# Sheet_SiPM.net
KiCad netlist of a schematic drawn in Altium Designer
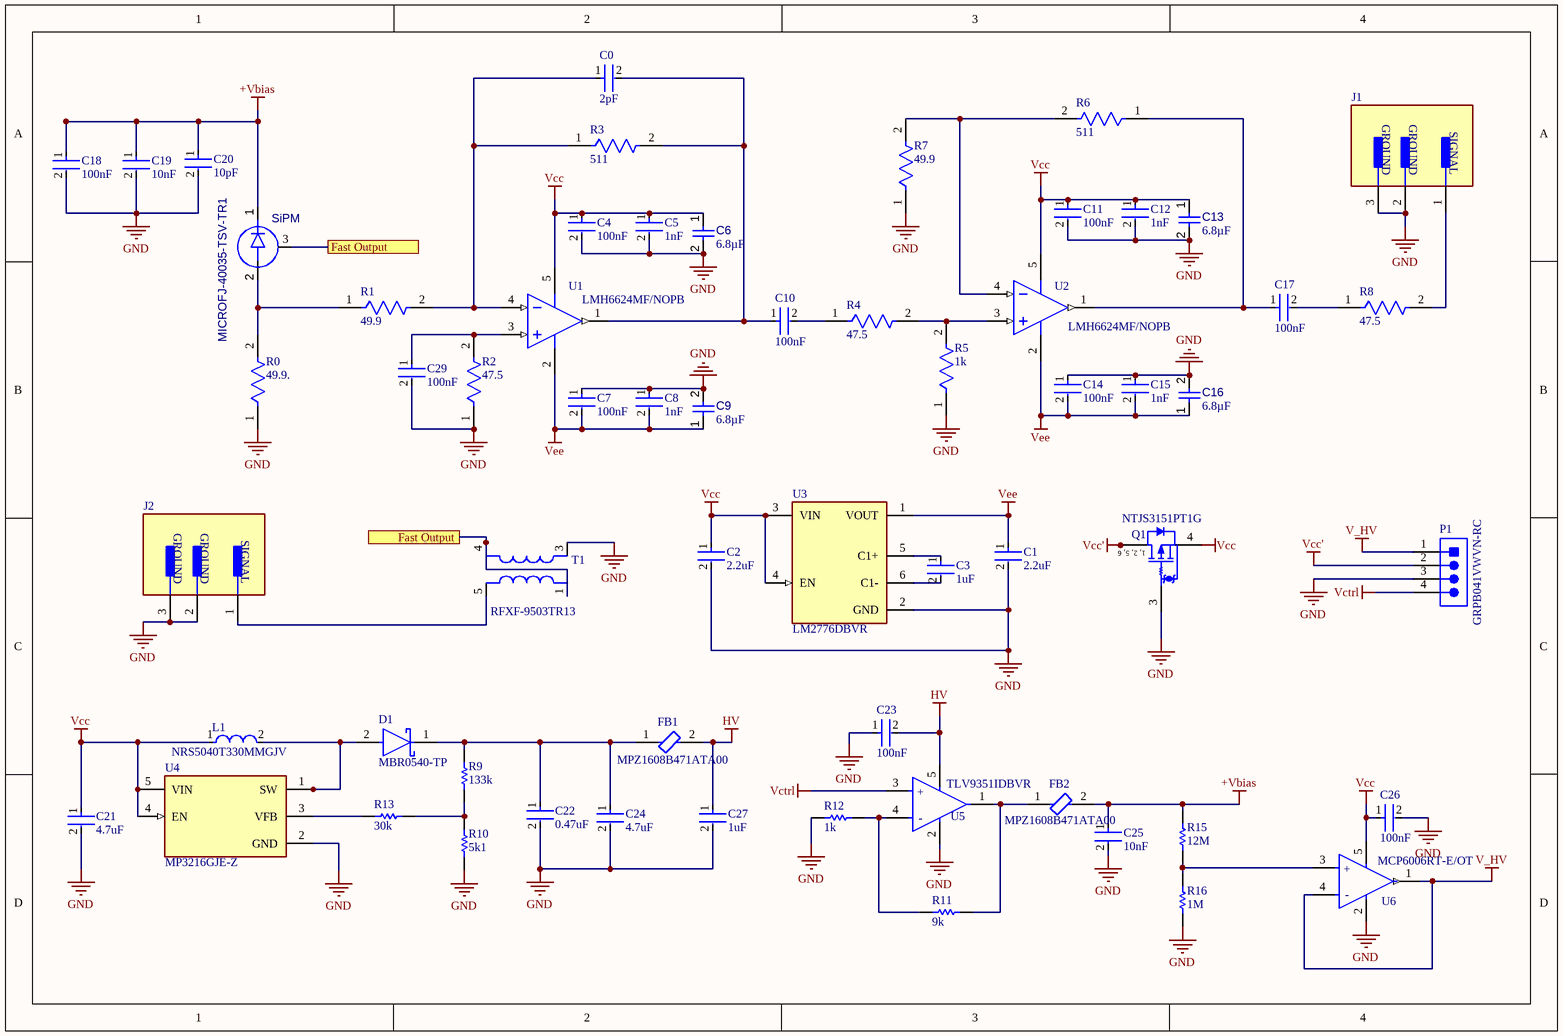
[diagram p0: Sheet_SiPM.SchDoc]

(export (version "E")
  (design (tool "Eeschema 10.0.6"))
  (components
    (comp (ref "C0")
      (value "2pF")
      (footprint "FP-0603-L_1_6_0_15-W_0_81-MFG")
      (description "General Purpose Ceramic Capacitor, 0603, 1pF, 0.1pF, NP0, 30ppm/°C, 50V")
      (libsource (lib "Altium Content Vault") (part "02cd4be3c70576c341d710602a673aa"))
    )
    (comp (ref "C1")
      (value "2.2uF")
      (footprint "FP-GRM188-0_2-MFG")
      (description "Chip Multilayer Ceramic Capacitors for General Purpose, 0603, 2.2uF, X7R, 15%, 10%, 16V")
      (libsource (lib "Altium Content Vault") (part "11868f565c42a9108669ba33697ecf6"))
    )
    (comp (ref "C2")
      (value "2.2uF")
      (footprint "FP-GRM188-0_2-MFG")
      (description "Chip Multilayer Ceramic Capacitors for General Purpose, 0603, 2.2uF, X7R, 15%, 10%, 16V")
      (libsource (lib "Altium Content Vault") (part "11868f565c42a9108669ba33697ecf6"))
    )
    (comp (ref "C3")
      (value "1uF")
      (footprint "FP-CC0603-DA-MFG")
      (description "CAP CER 1UF 16V X7R 0603")
      (fields (field (name "TOLERANCE") "0.1") (field (name "MANUFACTURER") "YAGEO"))
      (libsource (lib "Altium Content Vault") (part "11868f565c42a9108669ba33697ecf6"))
    )
    (comp (ref "C4")
      (value "100nF")
      (footprint "FP-CC0603-DA-MFG")
      (description "CAP CER 0.1UF 16V X7R 0603")
      (fields
        (field (name "OCTOPART") "https://octopart.com/cc0603krx7r7bb104-yageo-192941")
        (field (name "TOLERANCE") "0.1")
      )
      (libsource (lib "Altium Content Vault") (part "11868f565c42a9108669ba33697ecf6"))
    )
    (comp (ref "C5")
      (value "1nF")
      (footprint "FP-CC0603-DA-MFG")
      (description "CAP CER 1000PF 25V X7R 0603")
      (fields
        (field (name "MANUFACTURER") "YAGEO")
        (field (name "OCTOPART") "https://octopart.com/cc0603krx7r8bb102-yageo-9291798")
      )
      (libsource (lib "Altium Content Vault") (part "11868f565c42a9108669ba33697ecf6"))
    )
    (comp (ref "C6")
      (value "6.8µF")
      (footprint "TPSA685K016R1500-Footprint-1")
      (fields (field (name "Comment") "TPSA685K016R1500"))
      (libsource (lib "Francisco Martinez") (part "CAP-NP-2"))
    )
    (comp (ref "C7")
      (value "100nF")
      (footprint "FP-CC0603-DA-MFG")
      (description "CAP CER 0.1UF 16V X7R 0603")
      (fields
        (field (name "OCTOPART") "https://octopart.com/cc0603krx7r7bb104-yageo-192941")
        (field (name "TOLERANCE") "0.1")
      )
      (libsource (lib "Altium Content Vault") (part "11868f565c42a9108669ba33697ecf6"))
    )
    (comp (ref "C8")
      (value "1nF")
      (footprint "FP-CC0603-DA-MFG")
      (description "CAP CER 1000PF 25V X7R 0603")
      (fields
        (field (name "MANUFACTURER") "YAGEO")
        (field (name "OCTOPART") "https://octopart.com/cc0603krx7r8bb102-yageo-9291798")
      )
      (libsource (lib "Altium Content Vault") (part "11868f565c42a9108669ba33697ecf6"))
    )
    (comp (ref "C9")
      (value "6.8µF")
      (footprint "TPSA685K016R1500-Footprint-1")
      (fields (field (name "Comment") "TPSA685K016R1500"))
      (libsource (lib "Francisco Martinez") (part "CAP-NP-2"))
    )
    (comp (ref "C10")
      (value "100nF")
      (footprint "FP-CC0603-DA-MFG")
      (description "CAP CER 0.1UF 16V X7R 0603")
      (fields
        (field (name "OCTOPART") "https://octopart.com/cc0603krx7r7bb104-yageo-192941")
        (field (name "TOLERANCE") "0.1")
      )
      (libsource (lib "Altium Content Vault") (part "11868f565c42a9108669ba33697ecf6"))
    )
    (comp (ref "C11")
      (value "100nF")
      (footprint "FP-CC0603-DA-MFG")
      (description "CAP CER 0.1UF 16V X7R 0603")
      (fields
        (field (name "OCTOPART") "https://octopart.com/cc0603krx7r7bb104-yageo-192941")
        (field (name "TOLERANCE") "0.1")
      )
      (libsource (lib "Altium Content Vault") (part "11868f565c42a9108669ba33697ecf6"))
    )
    (comp (ref "C12")
      (value "1nF")
      (footprint "FP-CC0603-DA-MFG")
      (description "CAP CER 1000PF 25V X7R 0603")
      (fields
        (field (name "MANUFACTURER") "YAGEO")
        (field (name "OCTOPART") "https://octopart.com/cc0603krx7r8bb102-yageo-9291798")
      )
      (libsource (lib "Altium Content Vault") (part "11868f565c42a9108669ba33697ecf6"))
    )
    (comp (ref "C13")
      (value "6.8µF")
      (footprint "TPSA685K016R1500-Footprint-1")
      (fields (field (name "Comment") "TPSA685K016R1500"))
      (libsource (lib "Francisco Martinez") (part "CAP-NP-2"))
    )
    (comp (ref "C14")
      (value "100nF")
      (footprint "FP-CC0603-DA-MFG")
      (description "CAP CER 0.1UF 16V X7R 0603")
      (fields
        (field (name "OCTOPART") "https://octopart.com/cc0603krx7r7bb104-yageo-192941")
        (field (name "TOLERANCE") "0.1")
      )
      (libsource (lib "Altium Content Vault") (part "11868f565c42a9108669ba33697ecf6"))
    )
    (comp (ref "C15")
      (value "1nF")
      (footprint "FP-CC0603-DA-MFG")
      (description "CAP CER 1000PF 25V X7R 0603")
      (fields
        (field (name "MANUFACTURER") "YAGEO")
        (field (name "OCTOPART") "https://octopart.com/cc0603krx7r8bb102-yageo-9291798")
      )
      (libsource (lib "Altium Content Vault") (part "11868f565c42a9108669ba33697ecf6"))
    )
    (comp (ref "C16")
      (value "6.8µF")
      (footprint "TPSA685K016R1500-Footprint-1")
      (fields (field (name "Comment") "TPSA685K016R1500"))
      (libsource (lib "Francisco Martinez") (part "CAP-NP-2"))
    )
    (comp (ref "C17")
      (value "100nF")
      (footprint "FP-CC0603-DA-MFG")
      (description "CAP CER 0.1UF 16V X7R 0603")
      (fields
        (field (name "OCTOPART") "https://octopart.com/cc0603krx7r7bb104-yageo-192941")
        (field (name "TOLERANCE") "0.1")
      )
      (libsource (lib "Altium Content Vault") (part "11868f565c42a9108669ba33697ecf6"))
    )
    (comp (ref "C18")
      (value "100nF")
      (footprint "FP-CC0603-DA-MFG")
      (description "CAP CER 0.1UF 50V X7R 0603")
      (fields (field (name "MANUFACTURER") "YAGEO") (field (name "VOLTAGE") "50 V"))
      (libsource (lib "Altium Content Vault") (part "11868f565c42a9108669ba33697ecf6"))
    )
    (comp (ref "C19")
      (value "10nF")
      (footprint "FP-CC0603-DA-MFG")
      (description "CAP CER 10000PF 50V X7R 0603")
      (fields (field (name "TOLERANCE") "0.1") (field (name "MANUFACTURER PART NUMBER") "CC0603KRX7R9BB103"))
      (libsource (lib "Altium Content Vault") (part "11868f565c42a9108669ba33697ecf6"))
    )
    (comp (ref "C20")
      (value "10pF")
      (footprint "FP-AC0603-MFG")
      (description "AC0603 10 pF NP0 1.00% 50 V")
      (fields
        (field (name "MANUFACTURER") "Yageo")
        (field (name "MANUFACTURER PART NUMBER") "AC0603FRNPO9BN100")
      )
      (libsource (lib "Altium Content Vault") (part "11868f565c42a9108669ba33697ecf6"))
    )
    (comp (ref "C21")
      (value "4.7uF")
      (footprint "FP-0603-L_1_6_0_1-W_0_8_0-MFG")
      (description "Ceramic Capacitor General Use 0.47uF ±10% 50V X7R 0603")
      (fields (field (name "VOLTAGE") "50V") (field (name "TOLERANCE") "10%"))
      (libsource (lib "Altium Content Vault") (part "02cd4be3c70576c341d710602a673aa"))
    )
    (comp (ref "C22")
      (value "0.47uF")
      (footprint "FP-0603-L_1_6_0_1-W_0_8_0-MFG")
      (description "Ceramic Capacitor General Use 0.47uF ±10% 50V X7R 0603")
      (fields (field (name "VOLTAGE") "50V") (field (name "TOLERANCE") "10%"))
      (libsource (lib "Altium Content Vault") (part "02cd4be3c70576c341d710602a673aa"))
    )
    (comp (ref "C23")
      (value "100nF")
      (footprint "FP-CC0603-DA-MFG")
      (description "CAP CER 0.1UF 50V X7R 0603")
      (fields (field (name "MANUFACTURER") "YAGEO") (field (name "VOLTAGE") "50 V"))
      (libsource (lib "Altium Content Vault") (part "11868f565c42a9108669ba33697ecf6"))
    )
    (comp (ref "C24")
      (value "4.7uF")
      (footprint "FP-0603-L_1_6_0_15-W_0_8-MFG")
      (description "Ceramic Capacitor General Use 1uF ±10% 50V X7R 0603")
      (fields (field (name "TOLERANCE") "10%"))
      (libsource (lib "Altium Content Vault") (part "11868f565c42a9108669ba33697ecf6"))
    )
    (comp (ref "C25")
      (value "10nF")
      (footprint "FP-CC0603-DA-MFG")
      (description "CAP CER 10000PF 50V X7R 0603")
      (fields (field (name "TOLERANCE") "0.1") (field (name "MANUFACTURER PART NUMBER") "CC0603KRX7R9BB103"))
      (libsource (lib "Altium Content Vault") (part "11868f565c42a9108669ba33697ecf6"))
    )
    (comp (ref "C26")
      (value "100nF")
      (footprint "FP-CC0603-DA-MFG")
      (description "CAP CER 0.1UF 16V X7R 0603")
      (fields
        (field (name "OCTOPART") "https://octopart.com/cc0603krx7r7bb104-yageo-192941")
        (field (name "TOLERANCE") "0.1")
      )
      (libsource (lib "Altium Content Vault") (part "11868f565c42a9108669ba33697ecf6"))
    )
    (comp (ref "C27")
      (value "1uF")
      (footprint "FP-CC0603-DA-MFG")
      (description "CAP CER 10000PF 50V X7R 0603")
      (fields (field (name "TOLERANCE") "0.1") (field (name "MANUFACTURER PART NUMBER") "CC0603KRX7R9BB103"))
      (libsource (lib "Altium Content Vault") (part "11868f565c42a9108669ba33697ecf6"))
    )
    (comp (ref "C29")
      (value "100nF")
      (footprint "FP-CC0603-DA-MFG")
      (description "CAP CER 0.1UF 16V X7R 0603")
      (fields
        (field (name "OCTOPART") "https://octopart.com/cc0603krx7r7bb104-yageo-192941")
        (field (name "TOLERANCE") "0.1")
      )
      (libsource (lib "Altium Content Vault") (part "11868f565c42a9108669ba33697ecf6"))
    )
    (comp (ref "D1")
      (value "MBR0540-TP")
      (footprint "FP-SOD-123-MFG")
      (description "DIODE SCHOTTKY 40V 500MA SOD123")
      (libsource (lib "Altium Content Vault") (part "1d6ec82d83fb6aee721767c19dac4b9"))
    )
    (comp (ref "FB1")
      (value "MPZ1608B471ATA00")
      (footprint "FP-MPZ1608-0_8-MFG")
      (description "Power line Ferrite Bead 470Ω @ 100MHz 1A DCR 0.15Ω SMD 0603")
      (fields (field (name "TOLERANCE") "25%"))
      (libsource (lib "Altium Content Vault") (part "5f30dd21d616792df468990f7003faa"))
    )
    (comp (ref "FB2")
      (value "MPZ1608B471ATA00")
      (footprint "FP-MPZ1608-0_8-MFG")
      (description "Power line Ferrite Bead 470Ω @ 100MHz 1A DCR 0.15Ω SMD 0603")
      (fields (field (name "TOLERANCE") "25%"))
      (libsource (lib "Altium Content Vault") (part "5f30dd21d616792df468990f7003faa"))
    )
    (comp (ref "J1")
      (value "2337019-1")
      (footprint "FP-2337019-1-MFG")
      (description "UMCC MICRO-COAX RECEPTACLE, GEN")
      (libsource (lib "Altium Content Vault") (part "3efd87c86022015edd7e825a7948772"))
    )
    (comp (ref "J2")
      (value "2337019-1")
      (footprint "FP-2337019-1-MFG")
      (description "UMCC MICRO-COAX RECEPTACLE, GEN")
      (libsource (lib "Altium Content Vault") (part "3efd87c86022015edd7e825a7948772"))
    )
    (comp (ref "L1")
      (value "NRS5040T330MMGJV")
      (footprint "FP-NR5040-H_4_0-MFG")
      (description "SMD Power Inductors for Automotive Applications 33uH ±20% 1.2A 0.234Ω")
      (fields (field (name "TOLERANCE") "20%"))
      (libsource (lib "Altium Content Vault") (part "725321dda6339637d4d059423bc1c3c"))
    )
    (comp (ref "P1")
      (value "GRPB041VWVN-RC")
      (footprint "SLIN-GRPB041VWVN-RC_V")
      (fields (field (name "MANUFACTURER") "Sullins"))
      (libsource (lib "Altium Content Vault") (part "CN-1P-M-R4"))
    )
    (comp (ref "Q1")
      (value "NTJS3151PT1G")
      (footprint "ONSC-SC70-6-419B-02_W_V")
      (fields (field (name "MANUFACTURER") "On Semiconductor"))
      (libsource (lib "Altium Content Vault") (part "ONSC-PMOS-6_D"))
    )
    (comp (ref "R0")
      (value "49.9.")
      (footprint "FP-RNCP0603-MFG")
      (description "49.9Ω ±1% 0.125W 0603 High Power Anti-Sulfur Thin Film Chip Resistor")
      (fields (field (name "TOLERANCE") "1%"))
      (libsource (lib "Altium Content Vault") (part "1029c3af85768c4190bb7ad29bc67b5"))
    )
    (comp (ref "R1")
      (value "49.9")
      (footprint "FP-RNCP0603-MFG")
      (description "49.9Ω ±1% 0.125W 0603 High Power Anti-Sulfur Thin Film Chip Resistor")
      (fields (field (name "TOLERANCE") "1%"))
      (libsource (lib "Altium Content Vault") (part "1029c3af85768c4190bb7ad29bc67b5"))
    )
    (comp (ref "R2")
      (value "47.5")
      (footprint "FP-RNCP0603-MFG")
      (description "47.5Ω ±1% 0.125W 0603 High Power Anti-Sulfur Thin Film Chip Resistor")
      (fields (field (name "TOLERANCE") "1%"))
      (libsource (lib "Altium Content Vault") (part "1029c3af85768c4190bb7ad29bc67b5"))
    )
    (comp (ref "R3")
      (value "511")
      (footprint "FP-MCT0603-MFG")
      (description "RES SMD 100 OHM 1% 1/8W 0603")
      (fields (field (name "TOLERANCE") "1%"))
      (libsource (lib "Altium Content Vault") (part "1029c3af85768c4190bb7ad29bc67b5"))
    )
    (comp (ref "R4")
      (value "47.5")
      (footprint "FP-RNCP0603-MFG")
      (description "47.5Ω ±1% 0.125W 0603 High Power Anti-Sulfur Thin Film Chip Resistor")
      (fields (field (name "TOLERANCE") "1%"))
      (libsource (lib "Altium Content Vault") (part "1029c3af85768c4190bb7ad29bc67b5"))
    )
    (comp (ref "R5")
      (value "1k")
      (footprint "FP-MCT0603-MFG")
      (description "RES SMD 100 OHM 1% 1/8W 0603")
      (fields (field (name "TOLERANCE") "1%"))
      (libsource (lib "Altium Content Vault") (part "1029c3af85768c4190bb7ad29bc67b5"))
    )
    (comp (ref "R6")
      (value "511")
      (footprint "FP-MCT0603-MFG")
      (description "RES SMD 100 OHM 1% 1/8W 0603")
      (fields (field (name "TOLERANCE") "1%"))
      (libsource (lib "Altium Content Vault") (part "1029c3af85768c4190bb7ad29bc67b5"))
    )
    (comp (ref "R7")
      (value "49.9")
      (footprint "FP-RNCP0603-MFG")
      (description "49.9Ω ±1% 0.125W 0603 High Power Anti-Sulfur Thin Film Chip Resistor")
      (fields (field (name "TOLERANCE") "1%"))
      (libsource (lib "Altium Content Vault") (part "1029c3af85768c4190bb7ad29bc67b5"))
    )
    (comp (ref "R8")
      (value "47.5")
      (footprint "FP-RNCP0603-MFG")
      (description "47.5Ω ±1% 0.125W 0603 High Power Anti-Sulfur Thin Film Chip Resistor")
      (fields (field (name "TOLERANCE") "1%"))
      (libsource (lib "Altium Content Vault") (part "1029c3af85768c4190bb7ad29bc67b5"))
    )
    (comp (ref "R9")
      (value "133k")
      (footprint "RESC2013X60X35LL10T20")
      (fields (field (name "MANUFACTURER") "Yageo") (field (name "PART NUMBER") "RC0805FR-071M05L"))
      (libsource (lib "Altium Content Vault") (part "RES"))
    )
    (comp (ref "R10")
      (value "5k1")
      (footprint "RESC2013X60X35LL10T20")
      (fields (field (name "MANUFACTURER") "Yageo") (field (name "PART NUMBER") "RC0805JR-0743KL"))
      (libsource (lib "Altium Content Vault") (part "RES"))
    )
    (comp (ref "R11")
      (value "9k")
      (footprint "RESC2013X60X35LL10T20")
      (fields (field (name "MANUFACTURER") "Yageo") (field (name "PART NUMBER") "RC0805FR-071M05L"))
      (libsource (lib "Altium Content Vault") (part "RES"))
    )
    (comp (ref "R12")
      (value "1k")
      (footprint "RESC2013X60X35LL10T20")
      (fields (field (name "MANUFACTURER") "Yageo") (field (name "PART NUMBER") "RC0805FR-071M05L"))
      (libsource (lib "Altium Content Vault") (part "RES"))
    )
    (comp (ref "R13")
      (value "30k")
      (footprint "RESC2013X60X35LL10T20")
      (fields (field (name "MANUFACTURER") "Yageo") (field (name "PART NUMBER") "RC0805JR-0743KL"))
      (libsource (lib "Altium Content Vault") (part "RES"))
    )
    (comp (ref "R15")
      (value "12M")
      (footprint "RESC2013X60X35LL10T20")
      (fields (field (name "MANUFACTURER") "Yageo") (field (name "PART NUMBER") "RC0805FR-071M05L"))
      (libsource (lib "Altium Content Vault") (part "RES"))
    )
    (comp (ref "R16")
      (value "1M")
      (footprint "RESC2013X60X35LL10T20")
      (fields (field (name "MANUFACTURER") "Yageo") (field (name "PART NUMBER") "RC0805FR-071M05L"))
      (libsource (lib "Altium Content Vault") (part "RES"))
    )
    (comp (ref "SiPM")
      (value "MICROFJ-40035-TSV-TR1")
      (description "Avalanche Photodiode")
      (libsource (lib "Francisco Martinez") (part "SiPM"))
    )
    (comp (ref "T1")
      (value "RFXF-9503TR13")
      (footprint "RFXF-9503TR13-Footprint-1")
      (description "SMT Transformer 3MHZ-3GHZ")
      (libsource (lib "Francisco Martinez") (part "RFXF-9503TR13"))
    )
    (comp (ref "U1")
      (value "LMH6624MF/NOPB")
      (footprint "DBV0005A_L")
      (description "Single/ Dual Ultra Low Noise Wideband Operational Amplifier, 5-pin SOT-23, Pb-Free")
      (fields (field (name "MANUFACTURER") "Texas Instruments"))
      (libsource (lib "Altium Content Vault") (part "AMP-OPA-LM7121-5"))
    )
    (comp (ref "U2")
      (value "LMH6624MF/NOPB")
      (footprint "DBV0005A_L")
      (description "Single/ Dual Ultra Low Noise Wideband Operational Amplifier, 5-pin SOT-23, Pb-Free")
      (fields (field (name "MANUFACTURER") "Texas Instruments"))
      (libsource (lib "Altium Content Vault") (part "AMP-OPA-LM7121-5"))
    )
    (comp (ref "U3")
      (value "LM2776DBVR")
      (footprint "FP-DBV0006A-MFG")
      (description "IC REG CHARGE PUMP INV SOT23")
      (fields
        (field (name "MANUFACTURER") "Texas Instruments")
        (field (name "OCTOPART") "https://octopart.com/lm2776dbvr-texas+instruments-58839919")
      )
      (libsource (lib "Altium Content Vault") (part "aa1f6f8daf1b38e6829d08268534e6c"))
    )
    (comp (ref "U4")
      (value "MP3216GJE-Z")
      (footprint "MP3216GJE-Z-Footprint-1")
      (description "Switching Regulator")
      (libsource (lib "Francisco Martinez") (part "MP3216GJE-Z-Symbol-1"))
    )
    (comp (ref "U5")
      (value "TLV9351IDBVR")
      (footprint "FP-DBV0005A-MFG")
      (description "OPAMP")
      (libsource (lib "Altium Content Vault") (part "303ad2592cc7899f5e1082e1d8e7095"))
    )
    (comp (ref "U6")
      (value "MCP6006RT-E/OT")
      (footprint "FP-C04-091-OT-MFG")
      (description "MCP6006RT-E/OT Operational Amplifier, 1 Func, 1600uV Offset-Max, CMOS, PDSO5")
      (libsource (lib "Altium Content Vault") (part "c8a8c153b9e84e05c1733c8ea85bdd9"))
    )
  )
  (nets
    (net (code "1") (name "+Vbias") (class "Default")
      (node (ref "C18") (pin "1") (pinfunction "1_1") (pintype "passive"))
      (node (ref "C19") (pin "1") (pinfunction "1_1") (pintype "passive"))
      (node (ref "C20") (pin "1") (pinfunction "1_1") (pintype "passive"))
      (node (ref "C25") (pin "1") (pinfunction "1_1") (pintype "passive"))
      (node (ref "FB2") (pin "2") (pinfunction "2_2") (pintype "passive"))
      (node (ref "R15") (pin "2") (pinfunction "2_2") (pintype "passive"))
      (node (ref "SiPM") (pin "1") (pinfunction "K_1") (pintype "passive"))
    )
    (net (code "2") (name "/Fast Output") (class "Default")
      (node (ref "SiPM") (pin "3") (pinfunction "F_3") (pintype "passive"))
      (node (ref "T1") (pin "1") (pinfunction "1_1") (pintype "passive"))
      (node (ref "T1") (pin "4") (pinfunction "4_4") (pintype "passive"))
    )
    (net (code "3") (name "GND") (class "Default")
      (node (ref "C1") (pin "2") (pinfunction "2_2") (pintype "passive"))
      (node (ref "C11") (pin "2") (pinfunction "2_2") (pintype "passive"))
      (node (ref "C12") (pin "2") (pinfunction "2_2") (pintype "passive"))
      (node (ref "C13") (pin "2") (pinfunction "2_2") (pintype "passive"))
      (node (ref "C14") (pin "1") (pinfunction "1_1") (pintype "passive"))
      (node (ref "C15") (pin "1") (pinfunction "1_1") (pintype "passive"))
      (node (ref "C16") (pin "2") (pinfunction "2_2") (pintype "passive"))
      (node (ref "C18") (pin "2") (pinfunction "2_2") (pintype "passive"))
      (node (ref "C19") (pin "2") (pinfunction "2_2") (pintype "passive"))
      (node (ref "C2") (pin "2") (pinfunction "2_2") (pintype "passive"))
      (node (ref "C20") (pin "2") (pinfunction "2_2") (pintype "passive"))
      (node (ref "C21") (pin "2") (pinfunction "2_2") (pintype "passive"))
      (node (ref "C22") (pin "2") (pinfunction "2_2") (pintype "passive"))
      (node (ref "C23") (pin "1") (pinfunction "1_1") (pintype "passive"))
      (node (ref "C24") (pin "2") (pinfunction "2_2") (pintype "passive"))
      (node (ref "C25") (pin "2") (pinfunction "2_2") (pintype "passive"))
      (node (ref "C26") (pin "2") (pinfunction "2_2") (pintype "passive"))
      (node (ref "C27") (pin "2") (pinfunction "2_2") (pintype "passive"))
      (node (ref "C29") (pin "2") (pinfunction "2_2") (pintype "passive"))
      (node (ref "C4") (pin "2") (pinfunction "2_2") (pintype "passive"))
      (node (ref "C5") (pin "2") (pinfunction "2_2") (pintype "passive"))
      (node (ref "C6") (pin "2") (pinfunction "2_2") (pintype "passive"))
      (node (ref "C7") (pin "1") (pinfunction "1_1") (pintype "passive"))
      (node (ref "C8") (pin "1") (pinfunction "1_1") (pintype "passive"))
      (node (ref "C9") (pin "2") (pinfunction "2_2") (pintype "passive"))
      (node (ref "J1") (pin "2") (pinfunction "GROUND_2") (pintype "power_in"))
      (node (ref "J1") (pin "3") (pinfunction "GROUND_3") (pintype "power_in"))
      (node (ref "J2") (pin "2") (pinfunction "GROUND_2") (pintype "power_in"))
      (node (ref "J2") (pin "3") (pinfunction "GROUND_3") (pintype "power_in"))
      (node (ref "P1") (pin "3") (pinfunction "3_3") (pintype "passive"))
      (node (ref "Q1") (pin "3") (pinfunction "G_3") (pintype "passive"))
      (node (ref "R0") (pin "1") (pinfunction "1_1") (pintype "passive"))
      (node (ref "R10") (pin "1") (pinfunction "1_1") (pintype "passive"))
      (node (ref "R12") (pin "2") (pinfunction "2_2") (pintype "passive"))
      (node (ref "R16") (pin "1") (pinfunction "1_1") (pintype "passive"))
      (node (ref "R2") (pin "1") (pinfunction "1_1") (pintype "passive"))
      (node (ref "R5") (pin "1") (pinfunction "1_1") (pintype "passive"))
      (node (ref "R7") (pin "1") (pinfunction "1_1") (pintype "passive"))
      (node (ref "T1") (pin "3") (pinfunction "3_3") (pintype "passive"))
      (node (ref "U3") (pin "2") (pinfunction "GND_2") (pintype "power_in"))
      (node (ref "U4") (pin "2") (pinfunction "GND_2") (pintype "power_in"))
      (node (ref "U5") (pin "2") (pinfunction "V-_2") (pintype "power_in"))
      (node (ref "U6") (pin "2") (pinfunction "VSS_2") (pintype "power_in"))
    )
    (net (code "4") (name "HV") (class "Default")
      (node (ref "C23") (pin "2") (pinfunction "2_2") (pintype "passive"))
      (node (ref "C27") (pin "1") (pinfunction "1_1") (pintype "passive"))
      (node (ref "FB1") (pin "2") (pinfunction "2_2") (pintype "passive"))
      (node (ref "U5") (pin "5") (pinfunction "V+_5") (pintype "power_in"))
    )
    (net (code "5") (name "Net-(C10-Pad2)") (class "Default")
      (node (ref "C10") (pin "2") (pinfunction "2_2") (pintype "passive"))
      (node (ref "R4") (pin "1") (pinfunction "1_1") (pintype "passive"))
    )
    (net (code "6") (name "Net-(C17-Pad2)") (class "Default")
      (node (ref "C17") (pin "2") (pinfunction "2_2") (pintype "passive"))
      (node (ref "R8") (pin "1") (pinfunction "1_1") (pintype "passive"))
    )
    (net (code "7") (name "Net-(D1-A)") (class "Default")
      (node (ref "D1") (pin "2") (pinfunction "A_2") (pintype "passive"))
      (node (ref "L1") (pin "2") (pinfunction "2_2") (pintype "passive"))
      (node (ref "U4") (pin "1") (pinfunction "SW_1") (pintype "passive"))
    )
    (net (code "8") (name "Net-(D1-C)") (class "Default")
      (node (ref "C22") (pin "1") (pinfunction "1_1") (pintype "passive"))
      (node (ref "C24") (pin "1") (pinfunction "1_1") (pintype "passive"))
      (node (ref "D1") (pin "1") (pinfunction "C_1") (pintype "passive"))
      (node (ref "FB1") (pin "1") (pinfunction "1_1") (pintype "passive"))
      (node (ref "R9") (pin "2") (pinfunction "2_2") (pintype "passive"))
    )
    (net (code "9") (name "Net-(J1-SIGNAL)") (class "Default")
      (node (ref "J1") (pin "1") (pinfunction "SIGNAL_1") (pintype "passive"))
      (node (ref "R8") (pin "2") (pinfunction "2_2") (pintype "passive"))
    )
    (net (code "10") (name "Net-(J2-SIGNAL)") (class "Default")
      (node (ref "J2") (pin "1") (pinfunction "SIGNAL_1") (pintype "passive"))
      (node (ref "T1") (pin "5") (pinfunction "5_5") (pintype "passive"))
    )
    (net (code "11") (name "Net-(R10-Pad2)") (class "Default")
      (node (ref "R10") (pin "2") (pinfunction "2_2") (pintype "passive"))
      (node (ref "R13") (pin "1") (pinfunction "1_1") (pintype "passive"))
      (node (ref "R9") (pin "1") (pinfunction "1_1") (pintype "passive"))
    )
    (net (code "12") (name "Net-(SiPM-A)") (class "Default")
      (node (ref "R0") (pin "2") (pinfunction "2_2") (pintype "passive"))
      (node (ref "R1") (pin "1") (pinfunction "1_1") (pintype "passive"))
      (node (ref "SiPM") (pin "2") (pinfunction "A_2") (pintype "passive"))
    )
    (net (code "13") (name "Net-(U1-IN+)") (class "Default")
      (node (ref "C29") (pin "1") (pinfunction "1_1") (pintype "passive"))
      (node (ref "R2") (pin "2") (pinfunction "2_2") (pintype "passive"))
      (node (ref "U1") (pin "3") (pinfunction "IN+_3") (pintype "input"))
    )
    (net (code "14") (name "Net-(U1-IN-)") (class "Default")
      (node (ref "C0") (pin "1") (pinfunction "1_1") (pintype "passive"))
      (node (ref "R1") (pin "2") (pinfunction "2_2") (pintype "passive"))
      (node (ref "R3") (pin "1") (pinfunction "1_1") (pintype "passive"))
      (node (ref "U1") (pin "4") (pinfunction "IN-_4") (pintype "input"))
    )
    (net (code "15") (name "Net-(U1-OUT)") (class "Default")
      (node (ref "C0") (pin "2") (pinfunction "2_2") (pintype "passive"))
      (node (ref "C10") (pin "1") (pinfunction "1_1") (pintype "passive"))
      (node (ref "R3") (pin "2") (pinfunction "2_2") (pintype "passive"))
      (node (ref "U1") (pin "1") (pinfunction "OUT_1") (pintype "output"))
    )
    (net (code "16") (name "Net-(U2-IN+)") (class "Default")
      (node (ref "R4") (pin "2") (pinfunction "2_2") (pintype "passive"))
      (node (ref "R5") (pin "2") (pinfunction "2_2") (pintype "passive"))
      (node (ref "U2") (pin "3") (pinfunction "IN+_3") (pintype "input"))
    )
    (net (code "17") (name "Net-(U2-IN-)") (class "Default")
      (node (ref "R6") (pin "2") (pinfunction "2_2") (pintype "passive"))
      (node (ref "R7") (pin "2") (pinfunction "2_2") (pintype "passive"))
      (node (ref "U2") (pin "4") (pinfunction "IN-_4") (pintype "input"))
    )
    (net (code "18") (name "Net-(U2-OUT)") (class "Default")
      (node (ref "C17") (pin "1") (pinfunction "1_1") (pintype "passive"))
      (node (ref "R6") (pin "1") (pinfunction "1_1") (pintype "passive"))
      (node (ref "U2") (pin "1") (pinfunction "OUT_1") (pintype "output"))
    )
    (net (code "19") (name "Net-(U3-C1+)") (class "Default")
      (node (ref "C3") (pin "1") (pinfunction "1_1") (pintype "passive"))
      (node (ref "U3") (pin "5") (pinfunction "C1+_5") (pintype "power_in"))
    )
    (net (code "20") (name "Net-(U3-C1-)") (class "Default")
      (node (ref "C3") (pin "2") (pinfunction "2_2") (pintype "passive"))
      (node (ref "U3") (pin "6") (pinfunction "C1-_6") (pintype "power_in"))
    )
    (net (code "21") (name "Net-(U4-VFB)") (class "Default")
      (node (ref "R13") (pin "2") (pinfunction "2_2") (pintype "passive"))
      (node (ref "U4") (pin "3") (pinfunction "VFB_3") (pintype "passive"))
    )
    (net (code "22") (name "Net-(U5-IN-)") (class "Default")
      (node (ref "R11") (pin "2") (pinfunction "2_2") (pintype "passive"))
      (node (ref "R12") (pin "1") (pinfunction "1_1") (pintype "passive"))
      (node (ref "U5") (pin "4") (pinfunction "IN-_4") (pintype "tri_state"))
    )
    (net (code "23") (name "Net-(U5-OUT)") (class "Default")
      (node (ref "FB2") (pin "1") (pinfunction "1_1") (pintype "passive"))
      (node (ref "R11") (pin "1") (pinfunction "1_1") (pintype "passive"))
      (node (ref "U5") (pin "1") (pinfunction "OUT_1") (pintype "passive"))
    )
    (net (code "24") (name "Net-(U6-VIN+)") (class "Default")
      (node (ref "R15") (pin "1") (pinfunction "1_1") (pintype "passive"))
      (node (ref "R16") (pin "2") (pinfunction "2_2") (pintype "passive"))
      (node (ref "U6") (pin "3") (pinfunction "VIN+_3") (pintype "power_in"))
    )
    (net (code "25") (name "V_HV") (class "Default")
      (node (ref "P1") (pin "1") (pinfunction "1_1") (pintype "passive"))
      (node (ref "U6") (pin "1") (pinfunction "VOUT_1") (pintype "output"))
      (node (ref "U6") (pin "4") (pinfunction "VIN-_4") (pintype "power_in"))
    )
    (net (code "26") (name "Vcc") (class "Default")
      (node (ref "C11") (pin "1") (pinfunction "1_1") (pintype "passive"))
      (node (ref "C12") (pin "1") (pinfunction "1_1") (pintype "passive"))
      (node (ref "C13") (pin "1") (pinfunction "1_1") (pintype "passive"))
      (node (ref "C2") (pin "1") (pinfunction "1_1") (pintype "passive"))
      (node (ref "C21") (pin "1") (pinfunction "1_1") (pintype "passive"))
      (node (ref "C26") (pin "1") (pinfunction "1_1") (pintype "passive"))
      (node (ref "C4") (pin "1") (pinfunction "1_1") (pintype "passive"))
      (node (ref "C5") (pin "1") (pinfunction "1_1") (pintype "passive"))
      (node (ref "C6") (pin "1") (pinfunction "1_1") (pintype "passive"))
      (node (ref "L1") (pin "1") (pinfunction "1_1") (pintype "passive"))
      (node (ref "Q1") (pin "4") (pinfunction "S_4") (pintype "passive"))
      (node (ref "U1") (pin "5") (pinfunction "V+_5") (pintype "power_in"))
      (node (ref "U2") (pin "5") (pinfunction "V+_5") (pintype "power_in"))
      (node (ref "U3") (pin "3") (pinfunction "VIN_3") (pintype "power_in"))
      (node (ref "U3") (pin "4") (pinfunction "EN_4") (pintype "input"))
      (node (ref "U4") (pin "4") (pinfunction "EN_4") (pintype "input"))
      (node (ref "U4") (pin "5") (pinfunction "VIN_5") (pintype "power_in"))
      (node (ref "U6") (pin "5") (pinfunction "VDD_5") (pintype "power_in"))
    )
    (net (code "27") (name "Vcc'") (class "Default")
      (node (ref "P1") (pin "2") (pinfunction "2_2") (pintype "passive"))
      (node (ref "Q1") (pin "1") (pinfunction "D_1") (pintype "passive"))
      (node (ref "Q1") (pin "2") (pinfunction "D_2") (pintype "passive"))
      (node (ref "Q1") (pin "5") (pinfunction "D_5") (pintype "passive"))
      (node (ref "Q1") (pin "6") (pinfunction "D_6") (pintype "passive"))
    )
    (net (code "28") (name "Vctrl") (class "Default")
      (node (ref "P1") (pin "4") (pinfunction "4_4") (pintype "passive"))
      (node (ref "U5") (pin "3") (pinfunction "IN+_3") (pintype "tri_state"))
    )
    (net (code "29") (name "Vee") (class "Default")
      (node (ref "C1") (pin "1") (pinfunction "1_1") (pintype "passive"))
      (node (ref "C14") (pin "2") (pinfunction "2_2") (pintype "passive"))
      (node (ref "C15") (pin "2") (pinfunction "2_2") (pintype "passive"))
      (node (ref "C16") (pin "1") (pinfunction "1_1") (pintype "passive"))
      (node (ref "C7") (pin "2") (pinfunction "2_2") (pintype "passive"))
      (node (ref "C8") (pin "2") (pinfunction "2_2") (pintype "passive"))
      (node (ref "C9") (pin "1") (pinfunction "1_1") (pintype "passive"))
      (node (ref "U1") (pin "2") (pinfunction "V-_2") (pintype "power_in"))
      (node (ref "U2") (pin "2") (pinfunction "V-_2") (pintype "power_in"))
      (node (ref "U3") (pin "1") (pinfunction "VOUT_1") (pintype "power_in"))
    )
  )
)
